# IsoSPI_V0_1.net
KiCad netlist of a schematic drawn in Altium Designer
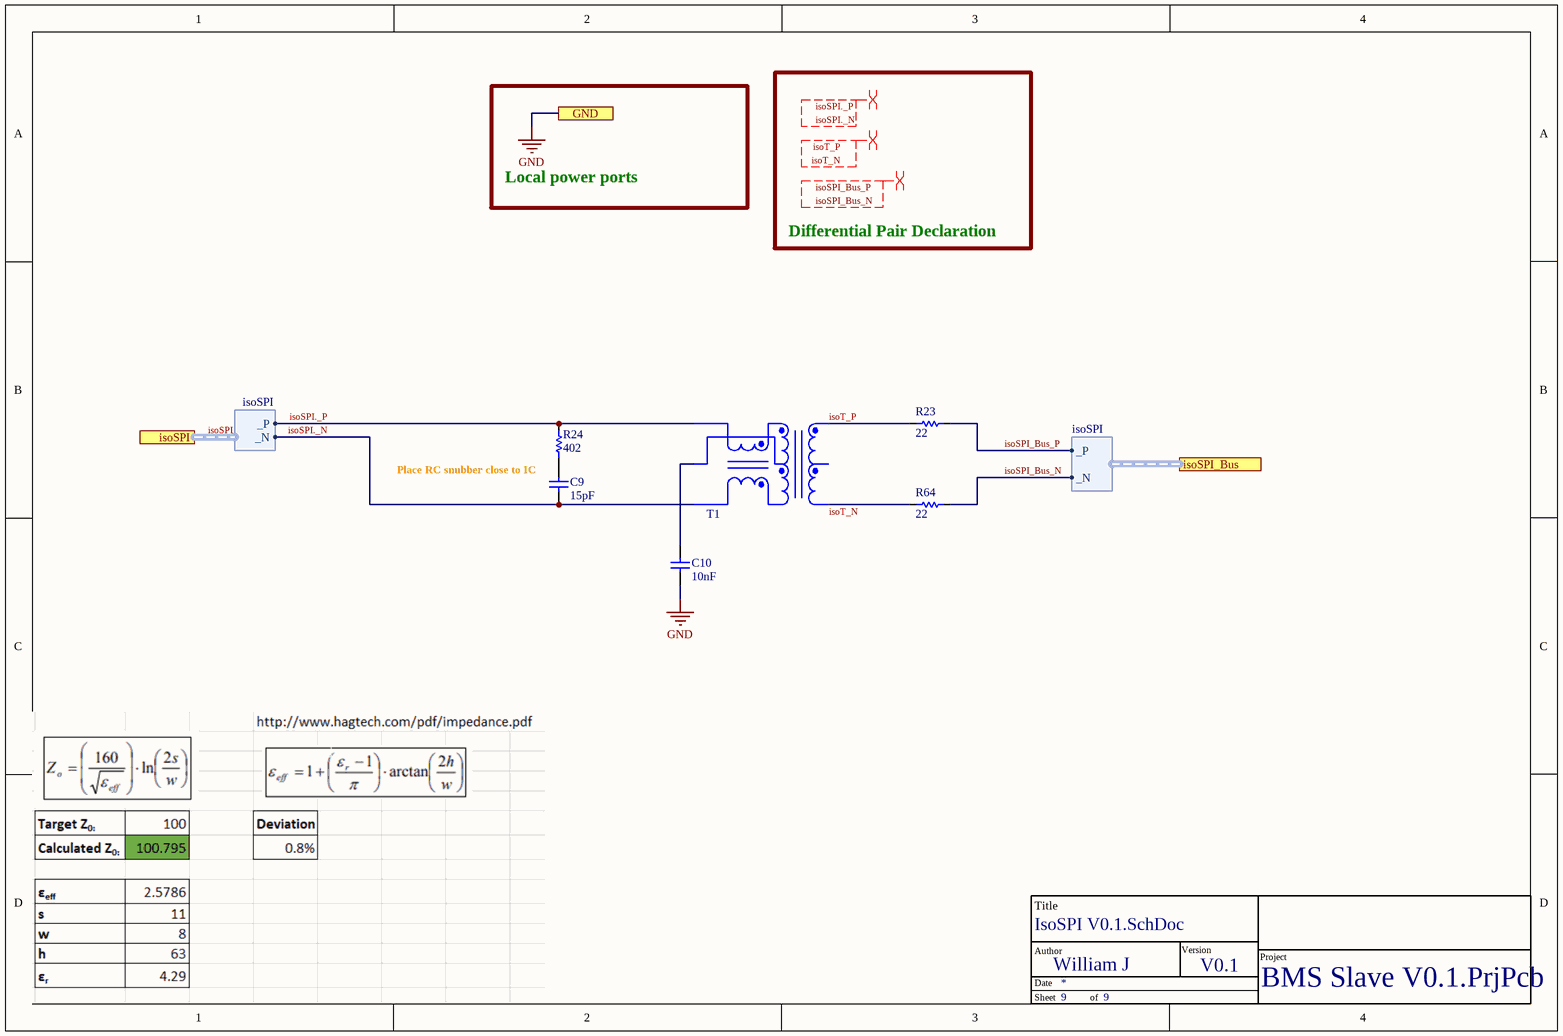
[diagram p0: IsoSPI V0.1.SchDoc]

(export (version "E")
  (design (tool "Eeschema 10.0.6"))
  (components
    (comp (ref "*") (value "TitleBlock") (libsource (lib "SchematicLib") (part "TitleBlock")))
    (comp (ref "C9")
      (value "15pF")
      (footprint "C_0402")
      (description "Capacitor")
      (fields (field (name "Comment") "885012005026"))
      (libsource (lib "Passives") (part "Capacitor"))
    )
    (comp (ref "C10")
      (value "10nF")
      (footprint "C_0402")
      (description "Capacitor")
      (fields (field (name "Comment") "C1005X7S2A103K050BB"))
      (libsource (lib "Passives") (part "Capacitor"))
    )
    (comp (ref "R23")
      (value "22")
      (footprint "R_0402")
      (description "Resistor")
      (fields (field (name "Comment") "RC0402JR-1322RL"))
      (libsource (lib "Passives") (part "Resistor"))
    )
    (comp (ref "R24")
      (value "402")
      (footprint "R_0402")
      (description "Resistor")
      (fields (field (name "Comment") "CRCW0402402RFKEDC"))
      (libsource (lib "Passives") (part "Resistor"))
    )
    (comp (ref "R64")
      (value "22")
      (footprint "R_0402")
      (description "Resistor")
      (fields (field (name "Comment") "RC0402JR-1322RL"))
      (libsource (lib "Passives") (part "Resistor"))
    )
    (comp (ref "T1")
      (value "SM91502ALE")
      (footprint "SM91502ALE")
      (description "BMS XFORMER 1-CH 1000V AECQ +125")
      (fields (field (name "MANUFACTURER") "Bourns"))
      (libsource (lib "SchematicLib") (part "SM91502ALE"))
    )
  )
  (nets
    (net (code "3") (name "/isoSPI._N") (class "Default")
      (node (ref "C9") (pin "1") (pinfunction "1_1") (pintype "passive"))
      (node (ref "T1") (pin "4") (pinfunction "4_4") (pintype "passive"))
    )
    (net (code "4") (name "/isoSPI._P") (class "Default")
      (node (ref "R24") (pin "2") (pinfunction "2_2") (pintype "passive"))
      (node (ref "T1") (pin "6") (pinfunction "6_6") (pintype "passive"))
    )
    (net (code "5") (name "/isoSPI_Bus_N") (class "Default")
      (node (ref "R64") (pin "1") (pinfunction "1_1") (pintype "passive"))
    )
    (net (code "6") (name "/isoSPI_Bus_P") (class "Default")
      (node (ref "R23") (pin "1") (pinfunction "1_1") (pintype "passive"))
    )
    (net (code "8") (name "/isoT_N") (class "Default")
      (node (ref "R64") (pin "2") (pinfunction "2_2") (pintype "passive"))
      (node (ref "T1") (pin "3") (pinfunction "3_3") (pintype "passive"))
    )
    (net (code "9") (name "/isoT_P") (class "Default")
      (node (ref "R23") (pin "2") (pinfunction "2_2") (pintype "passive"))
      (node (ref "T1") (pin "1") (pinfunction "1_1") (pintype "passive"))
    )
    (net (code "11") (name "GND") (class "Default")
      (node (ref "C10") (pin "1") (pinfunction "1_1") (pintype "passive"))
    )
    (net (code "12") (name "Net-(C9-Pad2)") (class "Default")
      (node (ref "C9") (pin "2") (pinfunction "2_2") (pintype "passive"))
      (node (ref "R24") (pin "1") (pinfunction "1_1") (pintype "passive"))
    )
    (net (code "13") (name "Net-(C10-Pad2)") (class "Default")
      (node (ref "C10") (pin "2") (pinfunction "2_2") (pintype "passive"))
      (node (ref "T1") (pin "5") (pinfunction "5_5") (pintype "passive"))
    )
    (net (code "14") (name "unconnected-(T1-Pad2)") (class "Default")
      (node (ref "T1") (pin "2") (pinfunction "2_2") (pintype "passive"))
    )
  )
)
